# test.net
KiCad netlist of a schematic drawn in EAGLE
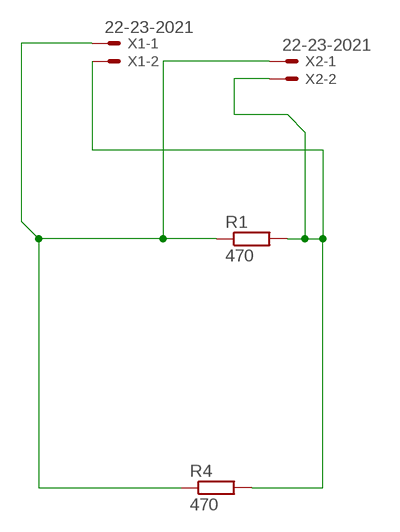
[diagram p0: schematic, sheet 1]

(export (version "E")
  (design (tool "Eeschema 10.0.6"))
  (components
    (comp (ref "R1")
      (value "470")
      (footprint "eagle-import:0207_10")
      (libsource (lib "eagle-import") (part "R-EU_0207/10"))
    )
    (comp (ref "R4")
      (value "470")
      (footprint "eagle-import:0207_10")
      (libsource (lib "eagle-import") (part "R-EU_0207/10"))
    )
    (comp (ref "X1")
      (value "22-23-2021")
      (footprint "eagle-import:22-23-2021")
      (fields (field (name "MF") "MOLEX"))
      (libsource (lib "eagle-import") (part "22-23-2021"))
    )
    (comp (ref "X2")
      (value "22-23-2021")
      (footprint "eagle-import:22-23-2021")
      (fields (field (name "MF") "MOLEX"))
      (libsource (lib "eagle-import") (part "22-23-2021"))
    )
  )
  (nets
    (net (code "1") (name "Net-(X1A-S)") (class "Default")
      (node (ref "R1") (pin "1") (pinfunction "1_1") (pintype "passive"))
      (node (ref "R4") (pin "1") (pinfunction "1_1") (pintype "passive"))
      (node (ref "X1") (pin "1") (pinfunction "S_1") (pintype "passive"))
      (node (ref "X2") (pin "1") (pinfunction "S_1") (pintype "passive"))
    )
    (net (code "2") (name "Net-(X1B-S)") (class "Default")
      (node (ref "R1") (pin "2") (pinfunction "2_2") (pintype "passive"))
      (node (ref "R4") (pin "2") (pinfunction "2_2") (pintype "passive"))
      (node (ref "X1") (pin "2") (pinfunction "S_2") (pintype "passive"))
      (node (ref "X2") (pin "2") (pinfunction "S_2") (pintype "passive"))
    )
  )
)
